# relay_shield3b.net
KiCad netlist of a schematic drawn in EAGLE
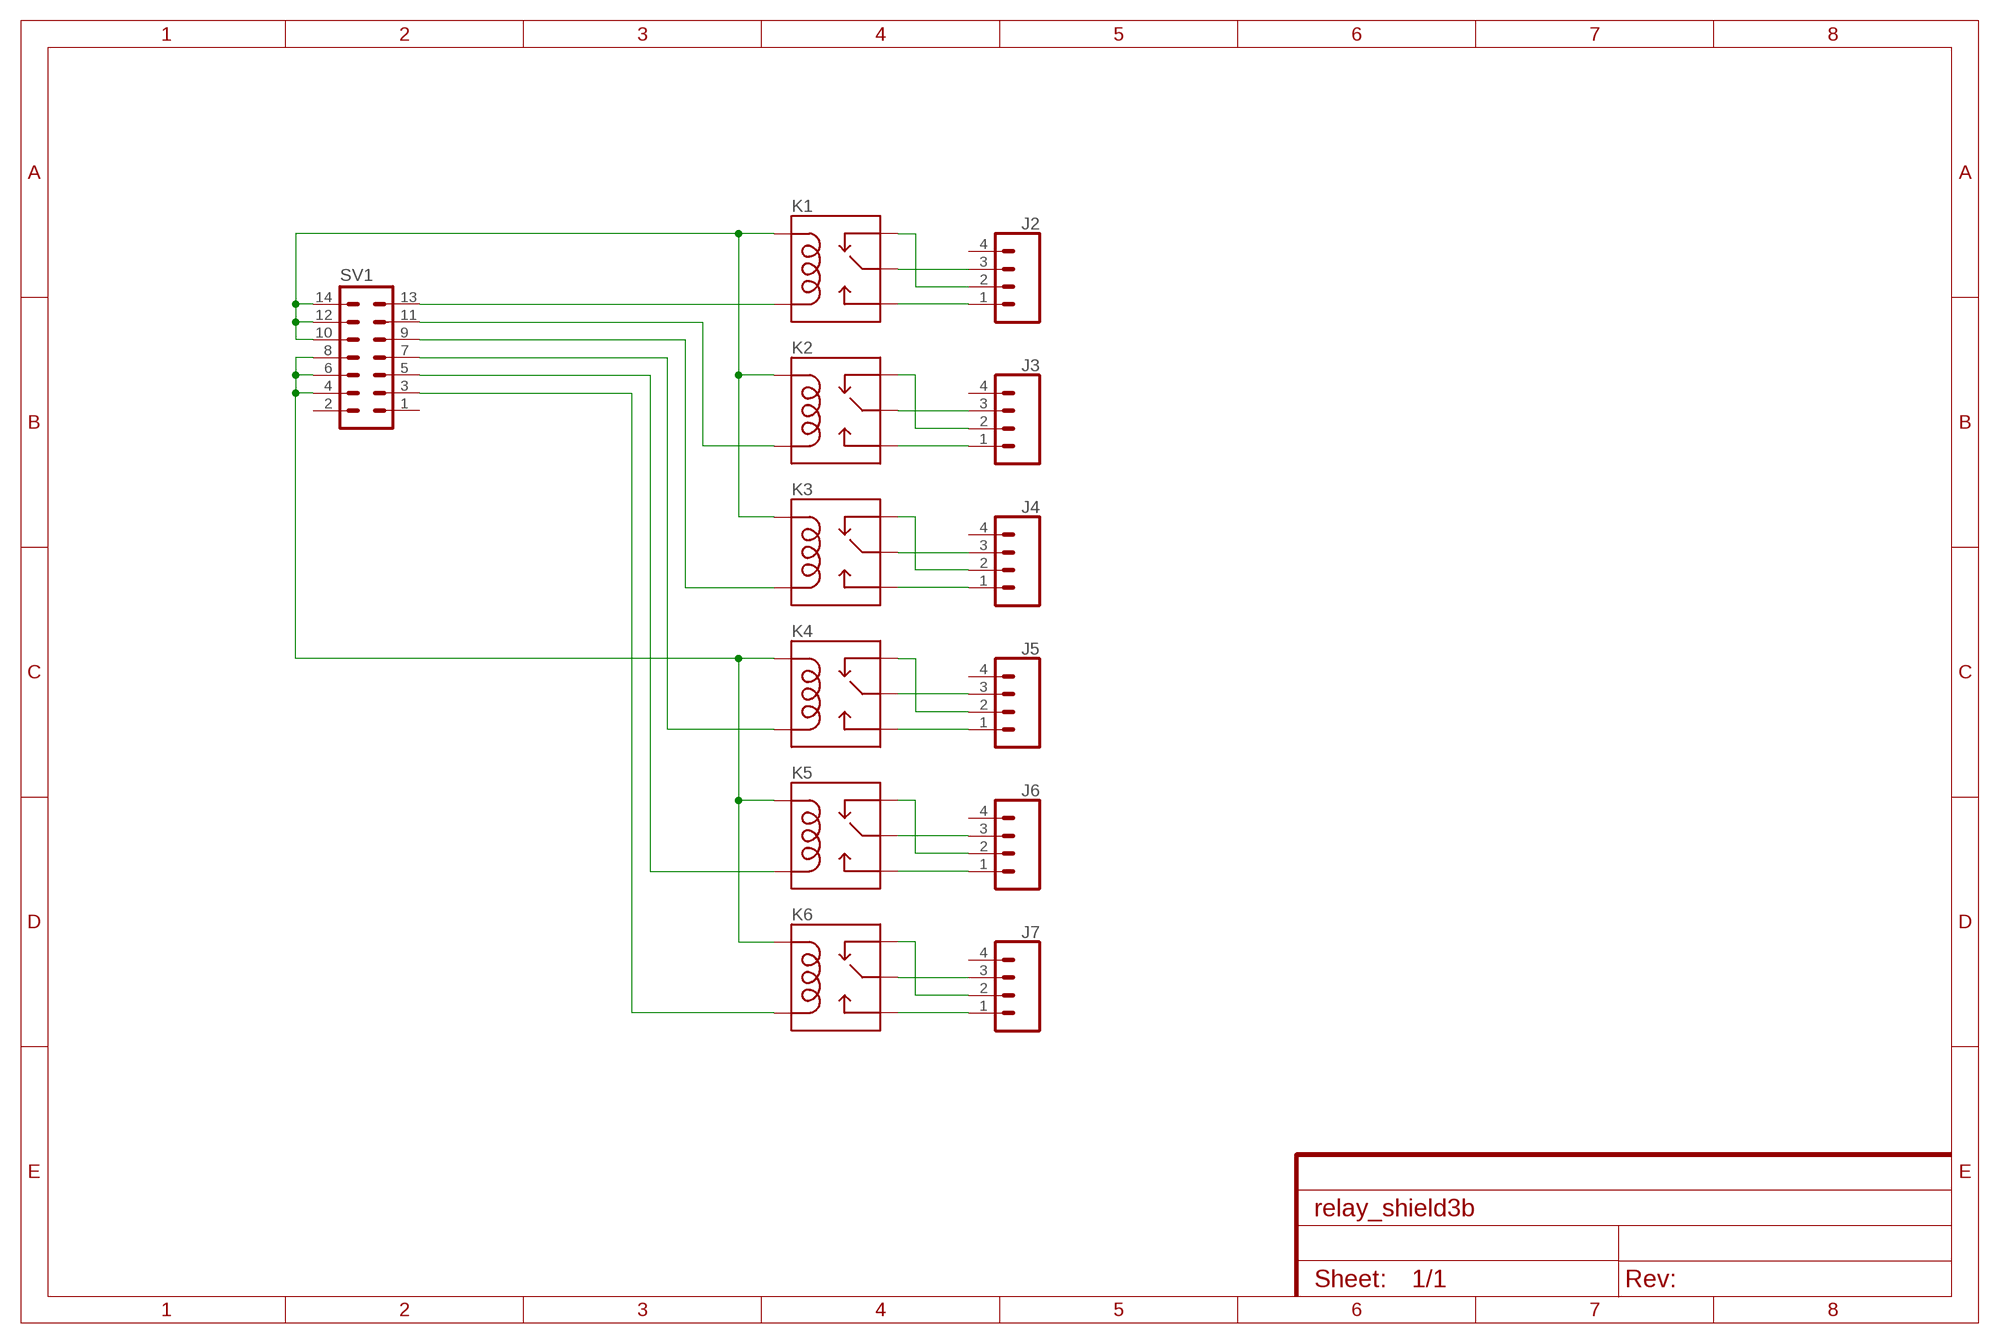
[diagram p0: schematic, sheet 1]

(export (version "E")
  (design (tool "Eeschema 10.0.6"))
  (components
    (comp (ref "J2")
      (value "CONN_04SCREW")
      (footprint "eagle-import:SCREWTERMINAL-3.5MM-4")
      (libsource (lib "eagle-import") (part "CONN_04SCREW"))
    )
    (comp (ref "J3")
      (value "CONN_04SCREW")
      (footprint "eagle-import:SCREWTERMINAL-3.5MM-4")
      (libsource (lib "eagle-import") (part "CONN_04SCREW"))
    )
    (comp (ref "J4")
      (value "CONN_04SCREW")
      (footprint "eagle-import:SCREWTERMINAL-3.5MM-4")
      (libsource (lib "eagle-import") (part "CONN_04SCREW"))
    )
    (comp (ref "J5")
      (value "CONN_04SCREW")
      (footprint "eagle-import:SCREWTERMINAL-3.5MM-4")
      (libsource (lib "eagle-import") (part "CONN_04SCREW"))
    )
    (comp (ref "J6")
      (value "CONN_04SCREW")
      (footprint "eagle-import:SCREWTERMINAL-3.5MM-4")
      (libsource (lib "eagle-import") (part "CONN_04SCREW"))
    )
    (comp (ref "J7")
      (value "CONN_04SCREW")
      (footprint "eagle-import:SCREWTERMINAL-3.5MM-4")
      (libsource (lib "eagle-import") (part "CONN_04SCREW"))
    )
    (comp (ref "K1")
      (value "RELAY-SPDTPTH6")
      (footprint "eagle-import:RELAY-SCHRACK-RY211")
      (libsource (lib "eagle-import") (part "RELAY-SPDTPTH6"))
    )
    (comp (ref "K2")
      (value "RELAY-SPDTPTH6")
      (footprint "eagle-import:RELAY-SCHRACK-RY211")
      (libsource (lib "eagle-import") (part "RELAY-SPDTPTH6"))
    )
    (comp (ref "K3")
      (value "RELAY-SPDTPTH6")
      (footprint "eagle-import:RELAY-SCHRACK-RY211")
      (libsource (lib "eagle-import") (part "RELAY-SPDTPTH6"))
    )
    (comp (ref "K4")
      (value "RELAY-SPDTPTH6")
      (footprint "eagle-import:RELAY-SCHRACK-RY211")
      (libsource (lib "eagle-import") (part "RELAY-SPDTPTH6"))
    )
    (comp (ref "K5")
      (value "RELAY-SPDTPTH6")
      (footprint "eagle-import:RELAY-SCHRACK-RY211")
      (libsource (lib "eagle-import") (part "RELAY-SPDTPTH6"))
    )
    (comp (ref "K6")
      (value "RELAY-SPDTPTH6")
      (footprint "eagle-import:RELAY-SCHRACK-RY211")
      (libsource (lib "eagle-import") (part "RELAY-SPDTPTH6"))
    )
    (comp (ref "SV1")
      (value "ML14L")
      (footprint "eagle-import:ML14L")
      (libsource (lib "eagle-import") (part "ML14L"))
    )
  )
  (nets
    (net (code "1") (name "Net-(K1-COIL1)") (class "Default")
      (node (ref "K1") (pin "A1") (pinfunction "COIL1_A1") (pintype "bidirectional"))
      (node (ref "K2") (pin "A1") (pinfunction "COIL1_A1") (pintype "bidirectional"))
      (node (ref "K3") (pin "A1") (pinfunction "COIL1_A1") (pintype "bidirectional"))
      (node (ref "SV1") (pin "10") (pinfunction "10_10") (pintype "passive"))
      (node (ref "SV1") (pin "12") (pinfunction "12_12") (pintype "passive"))
      (node (ref "SV1") (pin "14") (pinfunction "14_14") (pintype "passive"))
    )
    (net (code "2") (name "Net-(K1-COIL2)") (class "Default")
      (node (ref "K1") (pin "A2") (pinfunction "COIL2_A2") (pintype "bidirectional"))
      (node (ref "SV1") (pin "13") (pinfunction "13_13") (pintype "passive"))
    )
    (net (code "3") (name "Net-(K1-MAIN)") (class "Default")
      (node (ref "J2") (pin "3") (pinfunction "3_3") (pintype "passive"))
      (node (ref "K1") (pin "11") (pinfunction "MAIN_11") (pintype "bidirectional"))
    )
    (net (code "4") (name "Net-(K1-NC)") (class "Default")
      (node (ref "J2") (pin "2") (pinfunction "2_2") (pintype "passive"))
      (node (ref "K1") (pin "12") (pinfunction "NC_12") (pintype "bidirectional"))
    )
    (net (code "5") (name "Net-(K1-NO)") (class "Default")
      (node (ref "J2") (pin "1") (pinfunction "1_1") (pintype "passive"))
      (node (ref "K1") (pin "14") (pinfunction "NO_14") (pintype "bidirectional"))
    )
    (net (code "6") (name "Net-(K2-COIL2)") (class "Default")
      (node (ref "K2") (pin "A2") (pinfunction "COIL2_A2") (pintype "bidirectional"))
      (node (ref "SV1") (pin "11") (pinfunction "11_11") (pintype "passive"))
    )
    (net (code "7") (name "Net-(K2-MAIN)") (class "Default")
      (node (ref "J3") (pin "3") (pinfunction "3_3") (pintype "passive"))
      (node (ref "K2") (pin "11") (pinfunction "MAIN_11") (pintype "bidirectional"))
    )
    (net (code "8") (name "Net-(K2-NC)") (class "Default")
      (node (ref "J3") (pin "2") (pinfunction "2_2") (pintype "passive"))
      (node (ref "K2") (pin "12") (pinfunction "NC_12") (pintype "bidirectional"))
    )
    (net (code "9") (name "Net-(K2-NO)") (class "Default")
      (node (ref "J3") (pin "1") (pinfunction "1_1") (pintype "passive"))
      (node (ref "K2") (pin "14") (pinfunction "NO_14") (pintype "bidirectional"))
    )
    (net (code "10") (name "Net-(K3-COIL2)") (class "Default")
      (node (ref "K3") (pin "A2") (pinfunction "COIL2_A2") (pintype "bidirectional"))
      (node (ref "SV1") (pin "9") (pinfunction "9_9") (pintype "passive"))
    )
    (net (code "11") (name "Net-(K3-MAIN)") (class "Default")
      (node (ref "J4") (pin "3") (pinfunction "3_3") (pintype "passive"))
      (node (ref "K3") (pin "11") (pinfunction "MAIN_11") (pintype "bidirectional"))
    )
    (net (code "12") (name "Net-(K3-NC)") (class "Default")
      (node (ref "J4") (pin "2") (pinfunction "2_2") (pintype "passive"))
      (node (ref "K3") (pin "12") (pinfunction "NC_12") (pintype "bidirectional"))
    )
    (net (code "13") (name "Net-(K3-NO)") (class "Default")
      (node (ref "J4") (pin "1") (pinfunction "1_1") (pintype "passive"))
      (node (ref "K3") (pin "14") (pinfunction "NO_14") (pintype "bidirectional"))
    )
    (net (code "14") (name "Net-(K4-COIL1)") (class "Default")
      (node (ref "K4") (pin "A1") (pinfunction "COIL1_A1") (pintype "bidirectional"))
      (node (ref "K5") (pin "A1") (pinfunction "COIL1_A1") (pintype "bidirectional"))
      (node (ref "K6") (pin "A1") (pinfunction "COIL1_A1") (pintype "bidirectional"))
      (node (ref "SV1") (pin "4") (pinfunction "4_4") (pintype "passive"))
      (node (ref "SV1") (pin "6") (pinfunction "6_6") (pintype "passive"))
      (node (ref "SV1") (pin "8") (pinfunction "8_8") (pintype "passive"))
    )
    (net (code "15") (name "Net-(K4-COIL2)") (class "Default")
      (node (ref "K4") (pin "A2") (pinfunction "COIL2_A2") (pintype "bidirectional"))
      (node (ref "SV1") (pin "7") (pinfunction "7_7") (pintype "passive"))
    )
    (net (code "16") (name "Net-(K4-MAIN)") (class "Default")
      (node (ref "J5") (pin "3") (pinfunction "3_3") (pintype "passive"))
      (node (ref "K4") (pin "11") (pinfunction "MAIN_11") (pintype "bidirectional"))
    )
    (net (code "17") (name "Net-(K4-NC)") (class "Default")
      (node (ref "J5") (pin "2") (pinfunction "2_2") (pintype "passive"))
      (node (ref "K4") (pin "12") (pinfunction "NC_12") (pintype "bidirectional"))
    )
    (net (code "18") (name "Net-(K4-NO)") (class "Default")
      (node (ref "J5") (pin "1") (pinfunction "1_1") (pintype "passive"))
      (node (ref "K4") (pin "14") (pinfunction "NO_14") (pintype "bidirectional"))
    )
    (net (code "19") (name "Net-(K5-COIL2)") (class "Default")
      (node (ref "K5") (pin "A2") (pinfunction "COIL2_A2") (pintype "bidirectional"))
      (node (ref "SV1") (pin "5") (pinfunction "5_5") (pintype "passive"))
    )
    (net (code "20") (name "Net-(K5-MAIN)") (class "Default")
      (node (ref "J6") (pin "3") (pinfunction "3_3") (pintype "passive"))
      (node (ref "K5") (pin "11") (pinfunction "MAIN_11") (pintype "bidirectional"))
    )
    (net (code "21") (name "Net-(K5-NC)") (class "Default")
      (node (ref "J6") (pin "2") (pinfunction "2_2") (pintype "passive"))
      (node (ref "K5") (pin "12") (pinfunction "NC_12") (pintype "bidirectional"))
    )
    (net (code "22") (name "Net-(K5-NO)") (class "Default")
      (node (ref "J6") (pin "1") (pinfunction "1_1") (pintype "passive"))
      (node (ref "K5") (pin "14") (pinfunction "NO_14") (pintype "bidirectional"))
    )
    (net (code "23") (name "Net-(K6-COIL2)") (class "Default")
      (node (ref "K6") (pin "A2") (pinfunction "COIL2_A2") (pintype "bidirectional"))
      (node (ref "SV1") (pin "3") (pinfunction "3_3") (pintype "passive"))
    )
    (net (code "24") (name "Net-(K6-MAIN)") (class "Default")
      (node (ref "J7") (pin "3") (pinfunction "3_3") (pintype "passive"))
      (node (ref "K6") (pin "11") (pinfunction "MAIN_11") (pintype "bidirectional"))
    )
    (net (code "25") (name "Net-(K6-NC)") (class "Default")
      (node (ref "J7") (pin "2") (pinfunction "2_2") (pintype "passive"))
      (node (ref "K6") (pin "12") (pinfunction "NC_12") (pintype "bidirectional"))
    )
    (net (code "26") (name "Net-(K6-NO)") (class "Default")
      (node (ref "J7") (pin "1") (pinfunction "1_1") (pintype "passive"))
      (node (ref "K6") (pin "14") (pinfunction "NO_14") (pintype "bidirectional"))
    )
    (net (code "27") (name "unconnected-(J2-Pad4)") (class "Default")
      (node (ref "J2") (pin "4") (pinfunction "4_4") (pintype "passive"))
    )
    (net (code "28") (name "unconnected-(J3-Pad4)") (class "Default")
      (node (ref "J3") (pin "4") (pinfunction "4_4") (pintype "passive"))
    )
    (net (code "29") (name "unconnected-(J4-Pad4)") (class "Default")
      (node (ref "J4") (pin "4") (pinfunction "4_4") (pintype "passive"))
    )
    (net (code "30") (name "unconnected-(J5-Pad4)") (class "Default")
      (node (ref "J5") (pin "4") (pinfunction "4_4") (pintype "passive"))
    )
    (net (code "31") (name "unconnected-(J6-Pad4)") (class "Default")
      (node (ref "J6") (pin "4") (pinfunction "4_4") (pintype "passive"))
    )
    (net (code "32") (name "unconnected-(J7-Pad4)") (class "Default")
      (node (ref "J7") (pin "4") (pinfunction "4_4") (pintype "passive"))
    )
    (net (code "33") (name "unconnected-(SV1-Pad1)") (class "Default")
      (node (ref "SV1") (pin "1") (pinfunction "1_1") (pintype "passive"))
    )
    (net (code "34") (name "unconnected-(SV1-Pad2)") (class "Default")
      (node (ref "SV1") (pin "2") (pinfunction "2_2") (pintype "passive"))
    )
  )
)
